# MIDIWidgetRevD.net
KiCad netlist of a schematic drawn in EAGLE
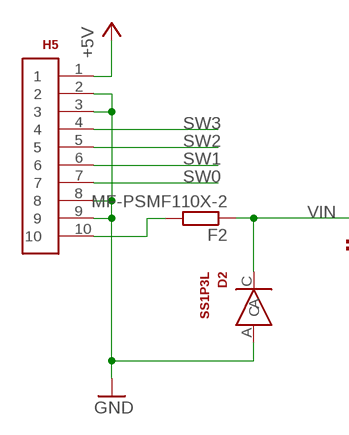
[diagram p0: schematic, sheet 1, part 1 of 2]
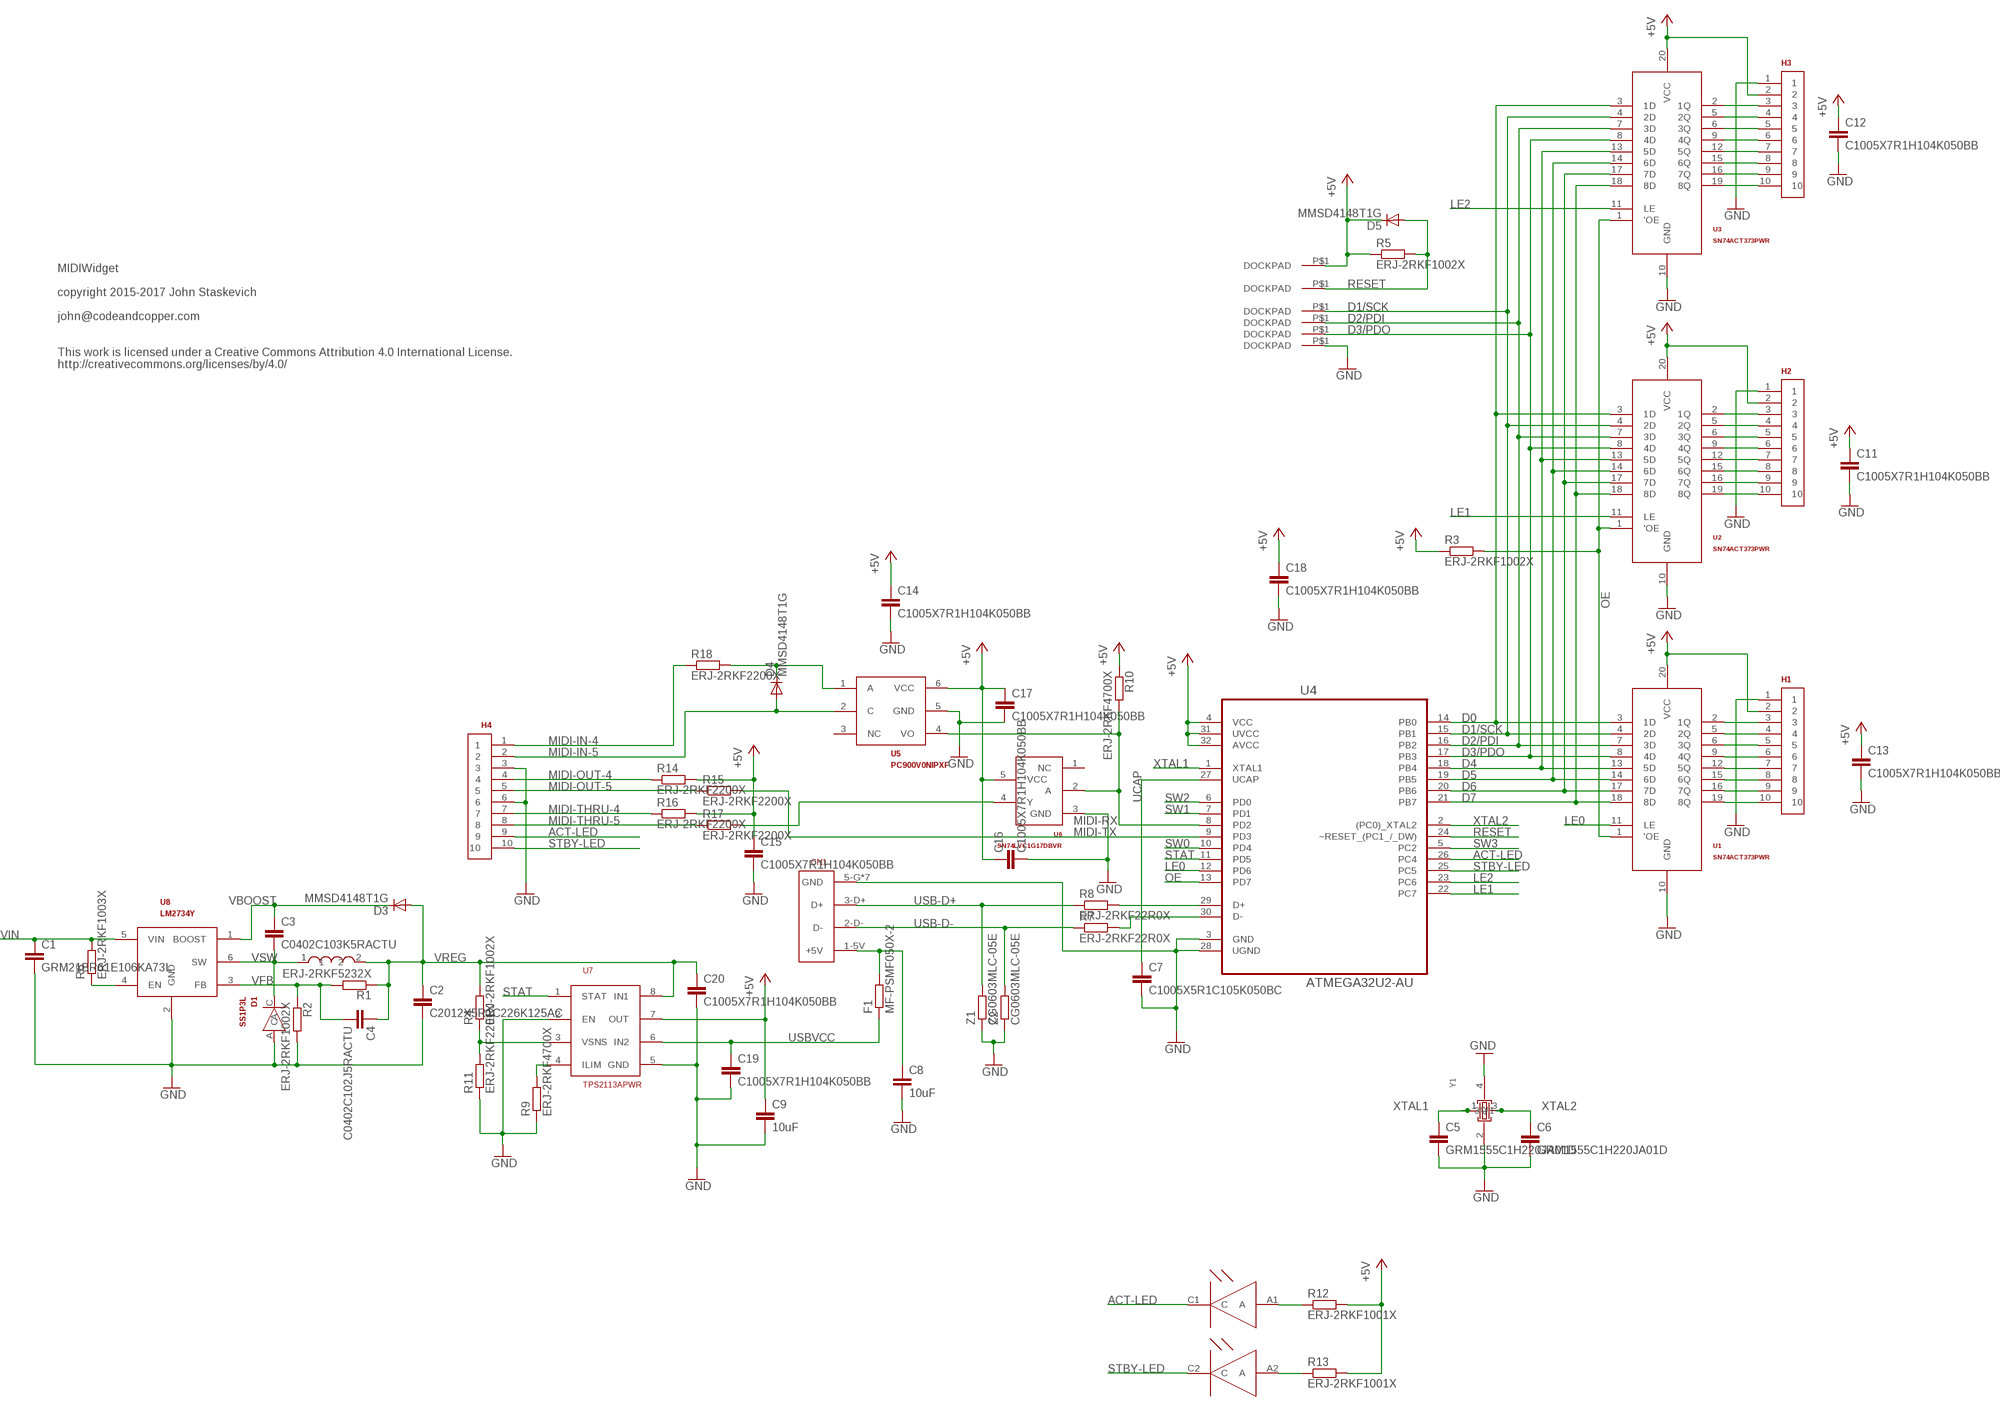
[diagram p1: schematic, sheet 1, part 2 of 2]

(export (version "E")
  (design (tool "Eeschema 10.0.6"))
  (components
    (comp (ref "C1")
      (value "GRM21BR61E106KA73L")
      (footprint "eagle-import:C0805")
      (libsource (lib "eagle-import") (part "C-EUC0805"))
    )
    (comp (ref "C2")
      (value "C2012X5R1C226K125AC")
      (footprint "eagle-import:C0805")
      (libsource (lib "eagle-import") (part "C-EUC0805"))
    )
    (comp (ref "C3")
      (value "C0402C103K5RACTU")
      (footprint "eagle-import:C0402")
      (libsource (lib "eagle-import") (part "C-EUC0402"))
    )
    (comp (ref "C4")
      (value "C0402C102J5RACTU")
      (footprint "eagle-import:C0402")
      (libsource (lib "eagle-import") (part "C-EUC0402"))
    )
    (comp (ref "C5")
      (value "GRM1555C1H220JA01D")
      (footprint "eagle-import:C0402")
      (libsource (lib "eagle-import") (part "C-EUC0402"))
    )
    (comp (ref "C6")
      (value "GRM1555C1H220JA01D")
      (footprint "eagle-import:C0402")
      (libsource (lib "eagle-import") (part "C-EUC0402"))
    )
    (comp (ref "C7")
      (value "C1005X5R1C105K050BC")
      (footprint "eagle-import:C0402")
      (libsource (lib "eagle-import") (part "C-EUC0402"))
    )
    (comp (ref "C8")
      (value "10uF")
      (footprint "eagle-import:C0805")
      (libsource (lib "eagle-import") (part "C-EUC0805"))
    )
    (comp (ref "C9")
      (value "10uF")
      (footprint "eagle-import:C0805")
      (libsource (lib "eagle-import") (part "C-EUC0805"))
    )
    (comp (ref "C11")
      (value "C1005X7R1H104K050BB")
      (footprint "eagle-import:C0402")
      (libsource (lib "eagle-import") (part "C-EUC0402"))
    )
    (comp (ref "C12")
      (value "C1005X7R1H104K050BB")
      (footprint "eagle-import:C0402")
      (libsource (lib "eagle-import") (part "C-EUC0402"))
    )
    (comp (ref "C13")
      (value "C1005X7R1H104K050BB")
      (footprint "eagle-import:C0402")
      (libsource (lib "eagle-import") (part "C-EUC0402"))
    )
    (comp (ref "C14")
      (value "C1005X7R1H104K050BB")
      (footprint "eagle-import:C0402")
      (libsource (lib "eagle-import") (part "C-EUC0402"))
    )
    (comp (ref "C15")
      (value "C1005X7R1H104K050BB")
      (footprint "eagle-import:C0402")
      (libsource (lib "eagle-import") (part "C-EUC0402"))
    )
    (comp (ref "C16")
      (value "C1005X7R1H104K050BB")
      (footprint "eagle-import:C0402")
      (libsource (lib "eagle-import") (part "C-EUC0402"))
    )
    (comp (ref "C17")
      (value "C1005X7R1H104K050BB")
      (footprint "eagle-import:C0402")
      (libsource (lib "eagle-import") (part "C-EUC0402"))
    )
    (comp (ref "C18")
      (value "C1005X7R1H104K050BB")
      (footprint "eagle-import:C0402")
      (libsource (lib "eagle-import") (part "C-EUC0402"))
    )
    (comp (ref "C19")
      (value "C1005X7R1H104K050BB")
      (footprint "eagle-import:C0402")
      (libsource (lib "eagle-import") (part "C-EUC0402"))
    )
    (comp (ref "C20")
      (value "C1005X7R1H104K050BB")
      (footprint "eagle-import:C0402")
      (libsource (lib "eagle-import") (part "C-EUC0402"))
    )
    (comp (ref "CN1")
      (value "10118192-0001LF")
      (footprint "eagle-import:USB-MICRO-B")
      (libsource (lib "eagle-import") (part "USB-B"))
    )
    (comp (ref "D1")
      (value "SS1P3L")
      (footprint "eagle-import:DO-220AA(SMP)")
      (libsource (lib "eagle-import") (part "DIODE"))
    )
    (comp (ref "D2")
      (value "SS1P3L")
      (footprint "eagle-import:DO-220AA(SMP)")
      (libsource (lib "eagle-import") (part "DIODE"))
    )
    (comp (ref "D3")
      (value "MMSD4148T1G")
      (footprint "eagle-import:SOD123")
      (libsource (lib "eagle-import") (part "1N4148SOD123"))
    )
    (comp (ref "D4")
      (value "MMSD4148T1G")
      (footprint "eagle-import:SOD123")
      (libsource (lib "eagle-import") (part "1N4148SOD123"))
    )
    (comp (ref "D5")
      (value "MMSD4148T1G")
      (footprint "eagle-import:SOD123")
      (libsource (lib "eagle-import") (part "1N4148SOD123"))
    )
    (comp (ref "DOCK-GND")
      (value "DOCKPAD")
      (footprint "eagle-import:DOCKPAD-ROUND-2.0MM")
      (libsource (lib "eagle-import") (part "DOCKPAD"))
    )
    (comp (ref "DOCK-PDI")
      (value "DOCKPAD")
      (footprint "eagle-import:DOCKPAD-ROUND-2.0MM")
      (libsource (lib "eagle-import") (part "DOCKPAD"))
    )
    (comp (ref "DOCK-PDO")
      (value "DOCKPAD")
      (footprint "eagle-import:DOCKPAD-ROUND-2.0MM")
      (libsource (lib "eagle-import") (part "DOCKPAD"))
    )
    (comp (ref "DOCK-RESET")
      (value "DOCKPAD")
      (footprint "eagle-import:DOCKPAD-ROUND-2.0MM")
      (libsource (lib "eagle-import") (part "DOCKPAD"))
    )
    (comp (ref "DOCK-SCK")
      (value "DOCKPAD")
      (footprint "eagle-import:DOCKPAD-ROUND-2.0MM")
      (libsource (lib "eagle-import") (part "DOCKPAD"))
    )
    (comp (ref "DOCK-VCC")
      (value "DOCKPAD")
      (footprint "eagle-import:DOCKPAD-ROUND-2.0MM")
      (libsource (lib "eagle-import") (part "DOCKPAD"))
    )
    (comp (ref "F1")
      (value "MF-PSMF050X-2")
      (footprint "eagle-import:R0805")
      (libsource (lib "eagle-import") (part "R-EU_R0805"))
    )
    (comp (ref "F2")
      (value "MF-PSMF110X-2")
      (footprint "eagle-import:R0805")
      (libsource (lib "eagle-import") (part "R-EU_R0805"))
    )
    (comp (ref "H1")
      (value "TERMINAL-BLOCK-10POS")
      (footprint "eagle-import:TB-2-54-10POS")
      (libsource (lib "eagle-import") (part "TERMINAL-BLOCK-10POS"))
    )
    (comp (ref "H2")
      (value "TERMINAL-BLOCK-10POS")
      (footprint "eagle-import:TB-2-54-10POS")
      (libsource (lib "eagle-import") (part "TERMINAL-BLOCK-10POS"))
    )
    (comp (ref "H3")
      (value "TERMINAL-BLOCK-10POS")
      (footprint "eagle-import:TB-2-54-10POS")
      (libsource (lib "eagle-import") (part "TERMINAL-BLOCK-10POS"))
    )
    (comp (ref "H4")
      (value "TERMINAL-BLOCK-10POS")
      (footprint "eagle-import:TB-2-54-10POS")
      (libsource (lib "eagle-import") (part "TERMINAL-BLOCK-10POS"))
    )
    (comp (ref "H5")
      (value "TERMINAL-BLOCK-10POS")
      (footprint "eagle-import:TB-2-54-10POS")
      (libsource (lib "eagle-import") (part "TERMINAL-BLOCK-10POS"))
    )
    (comp (ref "L1")
      (value "SLF7055T-220M1R7-3PF")
      (footprint "eagle-import:SLF7055")
      (libsource (lib "eagle-import") (part "INDUCTOR-SMT"))
    )
    (comp (ref "LED")
      (value "HSMF-C155")
      (footprint "eagle-import:LUMEX-1210-DUAL-LED")
      (libsource (lib "eagle-import") (part "DUAL-LED"))
    )
    (comp (ref "R1")
      (value "ERJ-2RKF5232X")
      (footprint "eagle-import:R0402")
      (libsource (lib "eagle-import") (part "R-EU_R0402"))
    )
    (comp (ref "R2")
      (value "ERJ-2RKF1002X")
      (footprint "eagle-import:R0402")
      (libsource (lib "eagle-import") (part "R-EU_R0402"))
    )
    (comp (ref "R3")
      (value "ERJ-2RKF1002X")
      (footprint "eagle-import:R0402")
      (libsource (lib "eagle-import") (part "R-EU_R0402"))
    )
    (comp (ref "R4")
      (value "ERJ-2RKF1002X")
      (footprint "eagle-import:R0402")
      (libsource (lib "eagle-import") (part "R-EU_R0402"))
    )
    (comp (ref "R5")
      (value "ERJ-2RKF1002X")
      (footprint "eagle-import:R0402")
      (libsource (lib "eagle-import") (part "R-EU_R0402"))
    )
    (comp (ref "R6")
      (value "ERJ-2RKF1003X")
      (footprint "eagle-import:R0402")
      (libsource (lib "eagle-import") (part "R-EU_R0402"))
    )
    (comp (ref "R7")
      (value "ERJ-2RKF22R0X")
      (footprint "eagle-import:R0402")
      (libsource (lib "eagle-import") (part "R-EU_R0402"))
    )
    (comp (ref "R8")
      (value "ERJ-2RKF22R0X")
      (footprint "eagle-import:R0402")
      (libsource (lib "eagle-import") (part "R-EU_R0402"))
    )
    (comp (ref "R9")
      (value "ERJ-2RKF4700X")
      (footprint "eagle-import:R0402")
      (libsource (lib "eagle-import") (part "R-EU_R0402"))
    )
    (comp (ref "R10")
      (value "ERJ-2RKF4700X")
      (footprint "eagle-import:R0402")
      (libsource (lib "eagle-import") (part "R-EU_R0402"))
    )
    (comp (ref "R11")
      (value "ERJ-2RKF2201X")
      (footprint "eagle-import:R0402")
      (libsource (lib "eagle-import") (part "R-EU_R0402"))
    )
    (comp (ref "R12")
      (value "ERJ-2RKF1001X")
      (footprint "eagle-import:R0402")
      (libsource (lib "eagle-import") (part "R-EU_R0402"))
    )
    (comp (ref "R13")
      (value "ERJ-2RKF1001X")
      (footprint "eagle-import:R0402")
      (libsource (lib "eagle-import") (part "R-EU_R0402"))
    )
    (comp (ref "R14")
      (value "ERJ-2RKF2200X")
      (footprint "eagle-import:R0402")
      (libsource (lib "eagle-import") (part "R-EU_R0402"))
    )
    (comp (ref "R15")
      (value "ERJ-2RKF2200X")
      (footprint "eagle-import:R0402")
      (libsource (lib "eagle-import") (part "R-EU_R0402"))
    )
    (comp (ref "R16")
      (value "ERJ-2RKF2200X")
      (footprint "eagle-import:R0402")
      (libsource (lib "eagle-import") (part "R-EU_R0402"))
    )
    (comp (ref "R17")
      (value "ERJ-2RKF2200X")
      (footprint "eagle-import:R0402")
      (libsource (lib "eagle-import") (part "R-EU_R0402"))
    )
    (comp (ref "R18")
      (value "ERJ-2RKF2200X")
      (footprint "eagle-import:R0402")
      (libsource (lib "eagle-import") (part "R-EU_R0402"))
    )
    (comp (ref "U1")
      (value "SN74ACT373PWR")
      (footprint "eagle-import:TSSOP-20")
      (libsource (lib "eagle-import") (part "74ABT373"))
    )
    (comp (ref "U2")
      (value "SN74ACT373PWR")
      (footprint "eagle-import:TSSOP-20")
      (libsource (lib "eagle-import") (part "74ABT373"))
    )
    (comp (ref "U3")
      (value "SN74ACT373PWR")
      (footprint "eagle-import:TSSOP-20")
      (libsource (lib "eagle-import") (part "74ABT373"))
    )
    (comp (ref "U4")
      (value "ATMEGA32U2-AU")
      (footprint "eagle-import:QFP80P900X900X120-32N")
      (libsource (lib "eagle-import") (part "ATMEGA32U2-AU"))
    )
    (comp (ref "U5")
      (value "PC900V0NIPXF")
      (footprint "eagle-import:SMT-6")
      (libsource (lib "eagle-import") (part "PC900V"))
    )
    (comp (ref "U6")
      (value "SN74LVC1G17DBVR")
      (footprint "eagle-import:SOT23-5-GOOD")
      (libsource (lib "eagle-import") (part "SN74LVC1G17"))
    )
    (comp (ref "U7")
      (value "TPS2113APWR")
      (footprint "eagle-import:TSSOP-8-NAKED")
      (libsource (lib "eagle-import") (part "TPS2112NAKED"))
    )
    (comp (ref "U8")
      (value "LM2734Y")
      (footprint "eagle-import:TSOT-6")
      (libsource (lib "eagle-import") (part "LM2734"))
    )
    (comp (ref "Y1")
      (value "403C35E16M00000")
      (footprint "eagle-import:CRYSTAL-32-25MM")
      (libsource (lib "eagle-import") (part "CTS-403-CRYSTAL"))
    )
    (comp (ref "Z1")
      (value "CG0603MLC-05E")
      (footprint "eagle-import:R0603")
      (libsource (lib "eagle-import") (part "R-EU_R0603"))
    )
    (comp (ref "Z2")
      (value "CG0603MLC-05E")
      (footprint "eagle-import:R0603")
      (libsource (lib "eagle-import") (part "R-EU_R0603"))
    )
  )
  (nets
    (net (code "1") (name "+5V") (class "Default")
      (node (ref "C11") (pin "1") (pinfunction "1_1") (pintype "passive"))
      (node (ref "C12") (pin "1") (pinfunction "1_1") (pintype "passive"))
      (node (ref "C13") (pin "1") (pinfunction "1_1") (pintype "passive"))
      (node (ref "C14") (pin "1") (pinfunction "1_1") (pintype "passive"))
      (node (ref "C15") (pin "1") (pinfunction "1_1") (pintype "passive"))
      (node (ref "C16") (pin "1") (pinfunction "1_1") (pintype "passive"))
      (node (ref "C17") (pin "1") (pinfunction "1_1") (pintype "passive"))
      (node (ref "C18") (pin "1") (pinfunction "1_1") (pintype "passive"))
      (node (ref "C9") (pin "1") (pinfunction "1_1") (pintype "passive"))
      (node (ref "D5") (pin "C") (pinfunction "C_C") (pintype "passive"))
      (node (ref "DOCK-VCC") (pin "P$1") (pinfunction "DOCKPAD_P$1") (pintype "bidirectional"))
      (node (ref "H1") (pin "2") (pinfunction "2_2") (pintype "bidirectional"))
      (node (ref "H2") (pin "2") (pinfunction "2_2") (pintype "bidirectional"))
      (node (ref "H3") (pin "2") (pinfunction "2_2") (pintype "bidirectional"))
      (node (ref "H5") (pin "1") (pinfunction "1_1") (pintype "bidirectional"))
      (node (ref "R10") (pin "1") (pinfunction "1_1") (pintype "passive"))
      (node (ref "R12") (pin "2") (pinfunction "2_2") (pintype "passive"))
      (node (ref "R13") (pin "2") (pinfunction "2_2") (pintype "passive"))
      (node (ref "R14") (pin "2") (pinfunction "2_2") (pintype "passive"))
      (node (ref "R16") (pin "2") (pinfunction "2_2") (pintype "passive"))
      (node (ref "R3") (pin "1") (pinfunction "1_1") (pintype "passive"))
      (node (ref "R5") (pin "1") (pinfunction "1_1") (pintype "passive"))
      (node (ref "U1") (pin "20") (pinfunction "VCC_20") (pintype "bidirectional"))
      (node (ref "U2") (pin "20") (pinfunction "VCC_20") (pintype "bidirectional"))
      (node (ref "U3") (pin "20") (pinfunction "VCC_20") (pintype "bidirectional"))
      (node (ref "U4") (pin "31") (pinfunction "UVCC_31") (pintype "power_in"))
      (node (ref "U4") (pin "32") (pinfunction "AVCC_32") (pintype "power_in"))
      (node (ref "U4") (pin "4") (pinfunction "VCC_4") (pintype "power_in"))
      (node (ref "U5") (pin "6") (pinfunction "VCC_6") (pintype "bidirectional"))
      (node (ref "U6") (pin "5") (pinfunction "VCC_5") (pintype "bidirectional"))
      (node (ref "U7") (pin "7") (pinfunction "OUT_7") (pintype "bidirectional"))
    )
    (net (code "2") (name "/ACT-LED") (class "Default")
      (node (ref "H4") (pin "9") (pinfunction "9_9") (pintype "bidirectional"))
      (node (ref "LED") (pin "C1") (pinfunction "C_C1") (pintype "bidirectional"))
      (node (ref "U4") (pin "26") (pinfunction "PC4_26") (pintype "bidirectional"))
    )
    (net (code "3") (name "/D0") (class "Default")
      (node (ref "U1") (pin "3") (pinfunction "1D_3") (pintype "bidirectional"))
      (node (ref "U2") (pin "3") (pinfunction "1D_3") (pintype "bidirectional"))
      (node (ref "U3") (pin "3") (pinfunction "1D_3") (pintype "bidirectional"))
      (node (ref "U4") (pin "14") (pinfunction "PB0_14") (pintype "bidirectional"))
    )
    (net (code "4") (name "/D1{slash}SCK") (class "Default")
      (node (ref "DOCK-SCK") (pin "P$1") (pinfunction "DOCKPAD_P$1") (pintype "bidirectional"))
      (node (ref "U1") (pin "4") (pinfunction "2D_4") (pintype "bidirectional"))
      (node (ref "U2") (pin "4") (pinfunction "2D_4") (pintype "bidirectional"))
      (node (ref "U3") (pin "4") (pinfunction "2D_4") (pintype "bidirectional"))
      (node (ref "U4") (pin "15") (pinfunction "PB1_15") (pintype "bidirectional"))
    )
    (net (code "5") (name "/D2{slash}PDI") (class "Default")
      (node (ref "DOCK-PDI") (pin "P$1") (pinfunction "DOCKPAD_P$1") (pintype "bidirectional"))
      (node (ref "U1") (pin "7") (pinfunction "3D_7") (pintype "bidirectional"))
      (node (ref "U2") (pin "7") (pinfunction "3D_7") (pintype "bidirectional"))
      (node (ref "U3") (pin "7") (pinfunction "3D_7") (pintype "bidirectional"))
      (node (ref "U4") (pin "16") (pinfunction "PB2_16") (pintype "bidirectional"))
    )
    (net (code "6") (name "/D3{slash}PDO") (class "Default")
      (node (ref "DOCK-PDO") (pin "P$1") (pinfunction "DOCKPAD_P$1") (pintype "bidirectional"))
      (node (ref "U1") (pin "8") (pinfunction "4D_8") (pintype "bidirectional"))
      (node (ref "U2") (pin "8") (pinfunction "4D_8") (pintype "bidirectional"))
      (node (ref "U3") (pin "8") (pinfunction "4D_8") (pintype "bidirectional"))
      (node (ref "U4") (pin "17") (pinfunction "PB3_17") (pintype "bidirectional"))
    )
    (net (code "7") (name "/D4") (class "Default")
      (node (ref "U1") (pin "13") (pinfunction "5D_13") (pintype "bidirectional"))
      (node (ref "U2") (pin "13") (pinfunction "5D_13") (pintype "bidirectional"))
      (node (ref "U3") (pin "13") (pinfunction "5D_13") (pintype "bidirectional"))
      (node (ref "U4") (pin "18") (pinfunction "PB4_18") (pintype "bidirectional"))
    )
    (net (code "8") (name "/D5") (class "Default")
      (node (ref "U1") (pin "14") (pinfunction "6D_14") (pintype "bidirectional"))
      (node (ref "U2") (pin "14") (pinfunction "6D_14") (pintype "bidirectional"))
      (node (ref "U3") (pin "14") (pinfunction "6D_14") (pintype "bidirectional"))
      (node (ref "U4") (pin "19") (pinfunction "PB5_19") (pintype "bidirectional"))
    )
    (net (code "9") (name "/D6") (class "Default")
      (node (ref "U1") (pin "17") (pinfunction "7D_17") (pintype "bidirectional"))
      (node (ref "U2") (pin "17") (pinfunction "7D_17") (pintype "bidirectional"))
      (node (ref "U3") (pin "17") (pinfunction "7D_17") (pintype "bidirectional"))
      (node (ref "U4") (pin "20") (pinfunction "PB6_20") (pintype "bidirectional"))
    )
    (net (code "10") (name "/D7") (class "Default")
      (node (ref "U1") (pin "18") (pinfunction "8D_18") (pintype "bidirectional"))
      (node (ref "U2") (pin "18") (pinfunction "8D_18") (pintype "bidirectional"))
      (node (ref "U3") (pin "18") (pinfunction "8D_18") (pintype "bidirectional"))
      (node (ref "U4") (pin "21") (pinfunction "PB7_21") (pintype "bidirectional"))
    )
    (net (code "11") (name "/LE0") (class "Default")
      (node (ref "U1") (pin "11") (pinfunction "LE_11") (pintype "bidirectional"))
      (node (ref "U4") (pin "12") (pinfunction "PD6_12") (pintype "bidirectional"))
    )
    (net (code "12") (name "/LE1") (class "Default")
      (node (ref "U2") (pin "11") (pinfunction "LE_11") (pintype "bidirectional"))
      (node (ref "U4") (pin "22") (pinfunction "PC7_22") (pintype "bidirectional"))
    )
    (net (code "13") (name "/LE2") (class "Default")
      (node (ref "U3") (pin "11") (pinfunction "LE_11") (pintype "bidirectional"))
      (node (ref "U4") (pin "23") (pinfunction "PC6_23") (pintype "bidirectional"))
    )
    (net (code "14") (name "/MIDI-IN-4") (class "Default")
      (node (ref "H4") (pin "1") (pinfunction "1_1") (pintype "bidirectional"))
      (node (ref "R18") (pin "1") (pinfunction "1_1") (pintype "passive"))
    )
    (net (code "15") (name "/MIDI-IN-5") (class "Default")
      (node (ref "D4") (pin "A") (pinfunction "A_A") (pintype "passive"))
      (node (ref "H4") (pin "2") (pinfunction "2_2") (pintype "bidirectional"))
      (node (ref "U5") (pin "2") (pinfunction "C_2") (pintype "bidirectional"))
    )
    (net (code "16") (name "/MIDI-OUT-4") (class "Default")
      (node (ref "H4") (pin "4") (pinfunction "4_4") (pintype "bidirectional"))
      (node (ref "R14") (pin "1") (pinfunction "1_1") (pintype "passive"))
    )
    (net (code "17") (name "/MIDI-OUT-5") (class "Default")
      (node (ref "H4") (pin "5") (pinfunction "5_5") (pintype "bidirectional"))
      (node (ref "R15") (pin "1") (pinfunction "1_1") (pintype "passive"))
    )
    (net (code "18") (name "/MIDI-RX") (class "Default")
      (node (ref "R10") (pin "2") (pinfunction "2_2") (pintype "passive"))
      (node (ref "U4") (pin "8") (pinfunction "PD2_8") (pintype "bidirectional"))
      (node (ref "U5") (pin "4") (pinfunction "VO_4") (pintype "bidirectional"))
      (node (ref "U6") (pin "2") (pinfunction "A_2") (pintype "bidirectional"))
    )
    (net (code "19") (name "/MIDI-THRU-4") (class "Default")
      (node (ref "H4") (pin "7") (pinfunction "7_7") (pintype "bidirectional"))
      (node (ref "R16") (pin "1") (pinfunction "1_1") (pintype "passive"))
    )
    (net (code "20") (name "/MIDI-THRU-5") (class "Default")
      (node (ref "H4") (pin "8") (pinfunction "8_8") (pintype "bidirectional"))
      (node (ref "R17") (pin "1") (pinfunction "1_1") (pintype "passive"))
    )
    (net (code "21") (name "/MIDI-TX") (class "Default")
      (node (ref "R15") (pin "2") (pinfunction "2_2") (pintype "passive"))
      (node (ref "U4") (pin "9") (pinfunction "PD3_9") (pintype "bidirectional"))
    )
    (net (code "22") (name "/OE") (class "Default")
      (node (ref "R3") (pin "2") (pinfunction "2_2") (pintype "passive"))
      (node (ref "U1") (pin "1") (pinfunction "'OE_1") (pintype "bidirectional"))
      (node (ref "U2") (pin "1") (pinfunction "'OE_1") (pintype "bidirectional"))
      (node (ref "U3") (pin "1") (pinfunction "'OE_1") (pintype "bidirectional"))
      (node (ref "U4") (pin "13") (pinfunction "PD7_13") (pintype "bidirectional"))
    )
    (net (code "23") (name "/RESET") (class "Default")
      (node (ref "D5") (pin "A") (pinfunction "A_A") (pintype "passive"))
      (node (ref "DOCK-RESET") (pin "P$1") (pinfunction "DOCKPAD_P$1") (pintype "bidirectional"))
      (node (ref "R5") (pin "2") (pinfunction "2_2") (pintype "passive"))
      (node (ref "U4") (pin "24") (pinfunction "~{RESET_(PC1_/_DW})_24") (pintype "bidirectional"))
    )
    (net (code "24") (name "/STAT") (class "Default")
      (node (ref "U4") (pin "11") (pinfunction "PD5_11") (pintype "bidirectional"))
      (node (ref "U7") (pin "1") (pinfunction "STAT_1") (pintype "bidirectional"))
    )
    (net (code "25") (name "/STBY-LED") (class "Default")
      (node (ref "H4") (pin "10") (pinfunction "10_10") (pintype "bidirectional"))
      (node (ref "LED") (pin "C2") (pinfunction "C_C2") (pintype "bidirectional"))
      (node (ref "U4") (pin "25") (pinfunction "PC5_25") (pintype "bidirectional"))
    )
    (net (code "26") (name "/SW0") (class "Default")
      (node (ref "H5") (pin "7") (pinfunction "7_7") (pintype "bidirectional"))
      (node (ref "U4") (pin "10") (pinfunction "PD4_10") (pintype "bidirectional"))
    )
    (net (code "27") (name "/SW1") (class "Default")
      (node (ref "H5") (pin "6") (pinfunction "6_6") (pintype "bidirectional"))
      (node (ref "U4") (pin "7") (pinfunction "PD1_7") (pintype "bidirectional"))
    )
    (net (code "28") (name "/SW2") (class "Default")
      (node (ref "H5") (pin "5") (pinfunction "5_5") (pintype "bidirectional"))
      (node (ref "U4") (pin "6") (pinfunction "PD0_6") (pintype "bidirectional"))
    )
    (net (code "29") (name "/SW3") (class "Default")
      (node (ref "H5") (pin "4") (pinfunction "4_4") (pintype "bidirectional"))
      (node (ref "U4") (pin "5") (pinfunction "PC2_5") (pintype "bidirectional"))
    )
    (net (code "30") (name "/UCAP") (class "Default")
      (node (ref "C7") (pin "1") (pinfunction "1_1") (pintype "passive"))
      (node (ref "U4") (pin "27") (pinfunction "UCAP_27") (pintype "power_in"))
    )
    (net (code "31") (name "/USB-D+") (class "Default")
      (node (ref "CN1") (pin "3-D+") (pinfunction "D+_3-D+") (pintype "bidirectional"))
      (node (ref "R8") (pin "1") (pinfunction "1_1") (pintype "passive"))
      (node (ref "Z1") (pin "2") (pinfunction "2_2") (pintype "passive"))
    )
    (net (code "32") (name "/USB-D-") (class "Default")
      (node (ref "CN1") (pin "2-D-") (pinfunction "D-_2-D-") (pintype "bidirectional"))
      (node (ref "R7") (pin "1") (pinfunction "1_1") (pintype "passive"))
      (node (ref "Z2") (pin "2") (pinfunction "2_2") (pintype "passive"))
    )
    (net (code "33") (name "/USBVCC") (class "Default")
      (node (ref "C19") (pin "1") (pinfunction "1_1") (pintype "passive"))
      (node (ref "F1") (pin "1") (pinfunction "1_1") (pintype "passive"))
      (node (ref "U7") (pin "6") (pinfunction "IN2_6") (pintype "bidirectional"))
    )
    (net (code "34") (name "/VBOOST") (class "Default")
      (node (ref "C3") (pin "1") (pinfunction "1_1") (pintype "passive"))
      (node (ref "D3") (pin "C") (pinfunction "C_C") (pintype "passive"))
      (node (ref "U8") (pin "1") (pinfunction "BOOST_1") (pintype "bidirectional"))
    )
    (net (code "35") (name "/VFB") (class "Default")
      (node (ref "C4") (pin "2") (pinfunction "2_2") (pintype "passive"))
      (node (ref "R1") (pin "2") (pinfunction "2_2") (pintype "passive"))
      (node (ref "R2") (pin "1") (pinfunction "1_1") (pintype "passive"))
      (node (ref "U8") (pin "3") (pinfunction "FB_3") (pintype "bidirectional"))
    )
    (net (code "36") (name "/VIN") (class "Default")
      (node (ref "C1") (pin "1") (pinfunction "1_1") (pintype "passive"))
      (node (ref "D2") (pin "C") (pinfunction "C_C") (pintype "bidirectional"))
      (node (ref "F2") (pin "1") (pinfunction "1_1") (pintype "passive"))
      (node (ref "R6") (pin "2") (pinfunction "2_2") (pintype "passive"))
      (node (ref "U8") (pin "5") (pinfunction "VIN_5") (pintype "bidirectional"))
    )
    (net (code "37") (name "/VREG") (class "Default")
      (node (ref "C2") (pin "1") (pinfunction "1_1") (pintype "passive"))
      (node (ref "C20") (pin "1") (pinfunction "1_1") (pintype "passive"))
      (node (ref "C4") (pin "1") (pinfunction "1_1") (pintype "passive"))
      (node (ref "D3") (pin "A") (pinfunction "A_A") (pintype "passive"))
      (node (ref "L1") (pin "2") (pinfunction "2_2") (pintype "bidirectional"))
      (node (ref "R1") (pin "1") (pinfunction "1_1") (pintype "passive"))
      (node (ref "R4") (pin "2") (pinfunction "2_2") (pintype "passive"))
      (node (ref "U7") (pin "8") (pinfunction "IN1_8") (pintype "bidirectional"))
    )
    (net (code "38") (name "/VSW") (class "Default")
      (node (ref "C3") (pin "2") (pinfunction "2_2") (pintype "passive"))
      (node (ref "D1") (pin "C") (pinfunction "C_C") (pintype "bidirectional"))
      (node (ref "L1") (pin "1") (pinfunction "1_1") (pintype "bidirectional"))
      (node (ref "U8") (pin "6") (pinfunction "SW_6") (pintype "bidirectional"))
    )
    (net (code "39") (name "/XTAL1") (class "Default")
      (node (ref "C5") (pin "1") (pinfunction "1_1") (pintype "passive"))
      (node (ref "U4") (pin "1") (pinfunction "XTAL1_1") (pintype "input"))
      (node (ref "Y1") (pin "1") (pinfunction "1_1") (pintype "bidirectional"))
    )
    (net (code "40") (name "/XTAL2") (class "Default")
      (node (ref "C6") (pin "1") (pinfunction "1_1") (pintype "passive"))
      (node (ref "U4") (pin "2") (pinfunction "(PC0)_XTAL2_2") (pintype "bidirectional"))
      (node (ref "Y1") (pin "3") (pinfunction "3_3") (pintype "bidirectional"))
    )
    (net (code "41") (name "GND") (class "Default")
      (node (ref "C1") (pin "2") (pinfunction "2_2") (pintype "passive"))
      (node (ref "C11") (pin "2") (pinfunction "2_2") (pintype "passive"))
      (node (ref "C12") (pin "2") (pinfunction "2_2") (pintype "passive"))
      (node (ref "C13") (pin "2") (pinfunction "2_2") (pintype "passive"))
      (node (ref "C14") (pin "2") (pinfunction "2_2") (pintype "passive"))
      (node (ref "C15") (pin "2") (pinfunction "2_2") (pintype "passive"))
      (node (ref "C16") (pin "2") (pinfunction "2_2") (pintype "passive"))
      (node (ref "C17") (pin "2") (pinfunction "2_2") (pintype "passive"))
      (node (ref "C18") (pin "2") (pinfunction "2_2") (pintype "passive"))
      (node (ref "C19") (pin "2") (pinfunction "2_2") (pintype "passive"))
      (node (ref "C2") (pin "2") (pinfunction "2_2") (pintype "passive"))
      (node (ref "C20") (pin "2") (pinfunction "2_2") (pintype "passive"))
      (node (ref "C5") (pin "2") (pinfunction "2_2") (pintype "passive"))
      (node (ref "C6") (pin "2") (pinfunction "2_2") (pintype "passive"))
      (node (ref "C7") (pin "2") (pinfunction "2_2") (pintype "passive"))
      (node (ref "C8") (pin "2") (pinfunction "2_2") (pintype "passive"))
      (node (ref "C9") (pin "2") (pinfunction "2_2") (pintype "passive"))
      (node (ref "CN1") (pin "5-G") (pinfunction "GND_5-G") (pintype "bidirectional"))
      (node (ref "CN1") (pin "P$1") (pinfunction "GND_P$1") (pintype "bidirectional"))
      (node (ref "CN1") (pin "P$10") (pinfunction "GND_P$10") (pintype "bidirectional"))
      (node (ref "CN1") (pin "P$11") (pinfunction "GND_P$11") (pintype "bidirectional"))
      (node (ref "CN1") (pin "P$2") (pinfunction "GND_P$2") (pintype "bidirectional"))
      (node (ref "CN1") (pin "P$3") (pinfunction "GND_P$3") (pintype "bidirectional"))
      (node (ref "CN1") (pin "P$4") (pinfunction "GND_P$4") (pintype "bidirectional"))
      (node (ref "D1") (pin "A") (pinfunction "A_A") (pintype "bidirectional"))
      (node (ref "D2") (pin "A") (pinfunction "A_A") (pintype "bidirectional"))
      (node (ref "DOCK-GND") (pin "P$1") (pinfunction "DOCKPAD_P$1") (pintype "bidirectional"))
      (node (ref "H1") (pin "1") (pinfunction "1_1") (pintype "bidirectional"))
      (node (ref "H2") (pin "1") (pinfunction "1_1") (pintype "bidirectional"))
      (node (ref "H3") (pin "1") (pinfunction "1_1") (pintype "bidirectional"))
      (node (ref "H4") (pin "3") (pinfunction "3_3") (pintype "bidirectional"))
      (node (ref "H4") (pin "6") (pinfunction "6_6") (pintype "bidirectional"))
      (node (ref "H5") (pin "2") (pinfunction "2_2") (pintype "bidirectional"))
      (node (ref "H5") (pin "3") (pinfunction "3_3") (pintype "bidirectional"))
      (node (ref "H5") (pin "8") (pinfunction "8_8") (pintype "bidirectional"))
      (node (ref "H5") (pin "9") (pinfunction "9_9") (pintype "bidirectional"))
      (node (ref "R11") (pin "1") (pinfunction "1_1") (pintype "passive"))
      (node (ref "R2") (pin "2") (pinfunction "2_2") (pintype "passive"))
      (node (ref "R9") (pin "1") (pinfunction "1_1") (pintype "passive"))
      (node (ref "U1") (pin "10") (pinfunction "GND_10") (pintype "bidirectional"))
      (node (ref "U2") (pin "10") (pinfunction "GND_10") (pintype "bidirectional"))
      (node (ref "U3") (pin "10") (pinfunction "GND_10") (pintype "bidirectional"))
      (node (ref "U4") (pin "28") (pinfunction "UGND_28") (pintype "passive"))
      (node (ref "U4") (pin "3") (pinfunction "GND_3") (pintype "passive"))
      (node (ref "U5") (pin "5") (pinfunction "GND_5") (pintype "bidirectional"))
      (node (ref "U6") (pin "3") (pinfunction "GND_3") (pintype "bidirectional"))
      (node (ref "U7") (pin "2") (pinfunction "EN_2") (pintype "bidirectional"))
      (node (ref "U7") (pin "5") (pinfunction "GND_5") (pintype "bidirectional"))
      (node (ref "U8") (pin "2") (pinfunction "GND_2") (pintype "bidirectional"))
      (node (ref "Y1") (pin "2") (pinfunction "2_2") (pintype "bidirectional"))
      (node (ref "Y1") (pin "4") (pinfunction "4_4") (pintype "bidirectional"))
      (node (ref "Z1") (pin "1") (pinfunction "1_1") (pintype "passive"))
      (node (ref "Z2") (pin "1") (pinfunction "1_1") (pintype "passive"))
    )
    (net (code "42") (name "Net-(CN1-+5V)") (class "Default")
      (node (ref "C8") (pin "1") (pinfunction "1_1") (pintype "passive"))
      (node (ref "CN1") (pin "1-5V") (pinfunction "+5V_1-5V") (pintype "bidirectional"))
      (node (ref "F1") (pin "2") (pinfunction "2_2") (pintype "passive"))
    )
    (net (code "43") (name "Net-(F2-Pad2)") (class "Default")
      (node (ref "F2") (pin "2") (pinfunction "2_2") (pintype "passive"))
      (node (ref "H5") (pin "10") (pinfunction "10_10") (pintype "bidirectional"))
    )
    (net (code "44") (name "Net-(LEDA-A)") (class "Default")
      (node (ref "LED") (pin "A1") (pinfunction "A_A1") (pintype "bidirectional"))
      (node (ref "R12") (pin "1") (pinfunction "1_1") (pintype "passive"))
    )
    (net (code "45") (name "Net-(LEDB-A)") (class "Default")
      (node (ref "LED") (pin "A2") (pinfunction "A_A2") (pintype "bidirectional"))
      (node (ref "R13") (pin "1") (pinfunction "1_1") (pintype "passive"))
    )
    (net (code "46") (name "Net-(U1-1Q)") (class "Default")
      (node (ref "H1") (pin "3") (pinfunction "3_3") (pintype "bidirectional"))
      (node (ref "U1") (pin "2") (pinfunction "1Q_2") (pintype "bidirectional"))
    )
    (net (code "47") (name "Net-(U1-2Q)") (class "Default")
      (node (ref "H1") (pin "4") (pinfunction "4_4") (pintype "bidirectional"))
      (node (ref "U1") (pin "5") (pinfunction "2Q_5") (pintype "bidirectional"))
    )
    (net (code "48") (name "Net-(U1-3Q)") (class "Default")
      (node (ref "H1") (pin "5") (pinfunction "5_5") (pintype "bidirectional"))
      (node (ref "U1") (pin "6") (pinfunction "3Q_6") (pintype "bidirectional"))
    )
    (net (code "49") (name "Net-(U1-4Q)") (class "Default")
      (node (ref "H1") (pin "6") (pinfunction "6_6") (pintype "bidirectional"))
      (node (ref "U1") (pin "9") (pinfunction "4Q_9") (pintype "bidirectional"))
    )
    (net (code "50") (name "Net-(U1-5Q)") (class "Default")
      (node (ref "H1") (pin "7") (pinfunction "7_7") (pintype "bidirectional"))
      (node (ref "U1") (pin "12") (pinfunction "5Q_12") (pintype "bidirectional"))
    )
    (net (code "51") (name "Net-(U1-6Q)") (class "Default")
      (node (ref "H1") (pin "8") (pinfunction "8_8") (pintype "bidirectional"))
      (node (ref "U1") (pin "15") (pinfunction "6Q_15") (pintype "bidirectional"))
    )
    (net (code "52") (name "Net-(U1-7Q)") (class "Default")
      (node (ref "H1") (pin "9") (pinfunction "9_9") (pintype "bidirectional"))
      (node (ref "U1") (pin "16") (pinfunction "7Q_16") (pintype "bidirectional"))
    )
    (net (code "53") (name "Net-(U1-8Q)") (class "Default")
      (node (ref "H1") (pin "10") (pinfunction "10_10") (pintype "bidirectional"))
      (node (ref "U1") (pin "19") (pinfunction "8Q_19") (pintype "bidirectional"))
    )
    (net (code "54") (name "Net-(U2-1Q)") (class "Default")
      (node (ref "H2") (pin "3") (pinfunction "3_3") (pintype "bidirectional"))
      (node (ref "U2") (pin "2") (pinfunction "1Q_2") (pintype "bidirectional"))
    )
    (net (code "55") (name "Net-(U2-2Q)") (class "Default")
      (node (ref "H2") (pin "4") (pinfunction "4_4") (pintype "bidirectional"))
      (node (ref "U2") (pin "5") (pinfunction "2Q_5") (pintype "bidirectional"))
    )
    (net (code "56") (name "Net-(U2-3Q)") (class "Default")
      (node (ref "H2") (pin "5") (pinfunction "5_5") (pintype "bidirectional"))
      (node (ref "U2") (pin "6") (pinfunction "3Q_6") (pintype "bidirectional"))
    )
    (net (code "57") (name "Net-(U2-4Q)") (class "Default")
      (node (ref "H2") (pin "6") (pinfunction "6_6") (pintype "bidirectional"))
      (node (ref "U2") (pin "9") (pinfunction "4Q_9") (pintype "bidirectional"))
    )
    (net (code "58") (name "Net-(U2-5Q)") (class "Default")
      (node (ref "H2") (pin "7") (pinfunction "7_7") (pintype "bidirectional"))
      (node (ref "U2") (pin "12") (pinfunction "5Q_12") (pintype "bidirectional"))
    )
    (net (code "59") (name "Net-(U2-6Q)") (class "Default")
      (node (ref "H2") (pin "8") (pinfunction "8_8") (pintype "bidirectional"))
      (node (ref "U2") (pin "15") (pinfunction "6Q_15") (pintype "bidirectional"))
    )
    (net (code "60") (name "Net-(U2-7Q)") (class "Default")
      (node (ref "H2") (pin "9") (pinfunction "9_9") (pintype "bidirectional"))
      (node (ref "U2") (pin "16") (pinfunction "7Q_16") (pintype "bidirectional"))
    )
    (net (code "61") (name "Net-(U2-8Q)") (class "Default")
      (node (ref "H2") (pin "10") (pinfunction "10_10") (pintype "bidirectional"))
      (node (ref "U2") (pin "19") (pinfunction "8Q_19") (pintype "bidirectional"))
    )
    (net (code "62") (name "Net-(U3-1Q)") (class "Default")
      (node (ref "H3") (pin "3") (pinfunction "3_3") (pintype "bidirectional"))
      (node (ref "U3") (pin "2") (pinfunction "1Q_2") (pintype "bidirectional"))
    )
    (net (code "63") (name "Net-(U3-2Q)") (class "Default")
      (node (ref "H3") (pin "4") (pinfunction "4_4") (pintype "bidirectional"))
      (node (ref "U3") (pin "5") (pinfunction "2Q_5") (pintype "bidirectional"))
    )
    (net (code "64") (name "Net-(U3-3Q)") (class "Default")
      (node (ref "H3") (pin "5") (pinfunction "5_5") (pintype "bidirectional"))
      (node (ref "U3") (pin "6") (pinfunction "3Q_6") (pintype "bidirectional"))
    )
    (net (code "65") (name "Net-(U3-4Q)") (class "Default")
      (node (ref "H3") (pin "6") (pinfunction "6_6") (pintype "bidirectional"))
      (node (ref "U3") (pin "9") (pinfunction "4Q_9") (pintype "bidirectional"))
    )
    (net (code "66") (name "Net-(U3-5Q)") (class "Default")
      (node (ref "H3") (pin "7") (pinfunction "7_7") (pintype "bidirectional"))
      (node (ref "U3") (pin "12") (pinfunction "5Q_12") (pintype "bidirectional"))
    )
    (net (code "67") (name "Net-(U3-6Q)") (class "Default")
      (node (ref "H3") (pin "8") (pinfunction "8_8") (pintype "bidirectional"))
      (node (ref "U3") (pin "15") (pinfunction "6Q_15") (pintype "bidirectional"))
    )
    (net (code "68") (name "Net-(U3-7Q)") (class "Default")
      (node (ref "H3") (pin "9") (pinfunction "9_9") (pintype "bidirectional"))
      (node (ref "U3") (pin "16") (pinfunction "7Q_16") (pintype "bidirectional"))
    )
    (net (code "69") (name "Net-(U3-8Q)") (class "Default")
      (node (ref "H3") (pin "10") (pinfunction "10_10") (pintype "bidirectional"))
      (node (ref "U3") (pin "19") (pinfunction "8Q_19") (pintype "bidirectional"))
    )
    (net (code "70") (name "Net-(U4-D+)") (class "Default")
      (node (ref "R8") (pin "2") (pinfunction "2_2") (pintype "passive"))
      (node (ref "U4") (pin "29") (pinfunction "D+_29") (pintype "bidirectional"))
    )
    (net (code "71") (name "Net-(U4-D-)") (class "Default")
      (node (ref "R7") (pin "2") (pinfunction "2_2") (pintype "passive"))
      (node (ref "U4") (pin "30") (pinfunction "D-_30") (pintype "bidirectional"))
    )
    (net (code "72") (name "Net-(U5-A)") (class "Default")
      (node (ref "D4") (pin "C") (pinfunction "C_C") (pintype "passive"))
      (node (ref "R18") (pin "2") (pinfunction "2_2") (pintype "passive"))
      (node (ref "U5") (pin "1") (pinfunction "A_1") (pintype "bidirectional"))
    )
    (net (code "73") (name "Net-(U6-Y)") (class "Default")
      (node (ref "R17") (pin "2") (pinfunction "2_2") (pintype "passive"))
      (node (ref "U6") (pin "4") (pinfunction "Y_4") (pintype "bidirectional"))
    )
    (net (code "74") (name "Net-(U7-ILIM)") (class "Default")
      (node (ref "R9") (pin "2") (pinfunction "2_2") (pintype "passive"))
      (node (ref "U7") (pin "4") (pinfunction "ILIM_4") (pintype "bidirectional"))
    )
    (net (code "75") (name "Net-(U7-VSNS)") (class "Default")
      (node (ref "R11") (pin "2") (pinfunction "2_2") (pintype "passive"))
      (node (ref "R4") (pin "1") (pinfunction "1_1") (pintype "passive"))
      (node (ref "U7") (pin "3") (pinfunction "VSNS_3") (pintype "bidirectional"))
    )
    (net (code "76") (name "Net-(U8-EN)") (class "Default")
      (node (ref "R6") (pin "1") (pinfunction "1_1") (pintype "passive"))
      (node (ref "U8") (pin "4") (pinfunction "EN_4") (pintype "bidirectional"))
    )
    (net (code "77") (name "unconnected-(U5-NC-Pad3)") (class "Default")
      (node (ref "U5") (pin "3") (pinfunction "NC_3") (pintype "bidirectional"))
    )
    (net (code "78") (name "unconnected-(U6-NC-Pad1)") (class "Default")
      (node (ref "U6") (pin "1") (pinfunction "NC_1") (pintype "bidirectional"))
    )
  )
)
